# Audio.net
KiCad netlist of a schematic drawn in Altium Designer
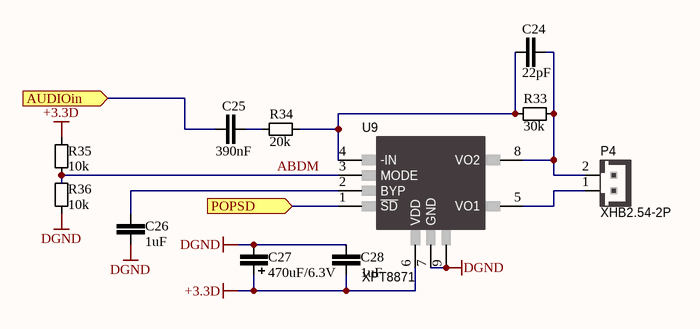
[diagram p0: Audio.SchDoc]

(export (version "E")
  (design (tool "Eeschema 10.0.6"))
  (components
    (comp (ref "C24")
      (value "22pF")
      (footprint "GreenBox:0603-C")
      (description "MLCC 22pF 5% 50V NPO 0603")
      (fields (field (name "Comment") "Cap") (field (name "PUBLISHER") "GreenBox"))
      (libsource (lib "Capacitor") (part "C11C022PJ1H0"))
    )
    (comp (ref "C25")
      (value "390nF")
      (footprint "GreenBox:0603-C")
      (description "MLCC 390nF 10% 50V X7R 0603")
      (fields (field (name "Comment") "Cap") (field (name "PUBLISHER") "GreenBox"))
      (libsource (lib "Capacitor") (part "C21C390NK1H0"))
    )
    (comp (ref "C26")
      (value "1uF")
      (footprint "GreenBox:0603-C")
      (description "MLCC 1uF 10% 16V X7R 0603")
      (fields (field (name "Comment") "Cap") (field (name "PUBLISHER") "GreenBox"))
      (libsource (lib "Capacitor") (part "C21C001UK1C0"))
    )
    (comp (ref "C27")
      (value "470uF/6.3V")
      (footprint "GreenBox:C-E-ALU-8X5")
      (description "DIP ECAP 470uF 20% 6.3V 8X5")
      (fields (field (name "Comment") "ECap") (field (name "PUBLISHER") "GreenBox"))
      (libsource (lib "Capacitor") (part "C3AD470UM0J0"))
    )
    (comp (ref "C28")
      (value "1uF")
      (footprint "GreenBox:0603-C")
      (description "MLCC 1uF 10% 16V X7R 0603")
      (fields (field (name "Comment") "Cap") (field (name "PUBLISHER") "GreenBox"))
      (libsource (lib "Capacitor") (part "C21C001UK1C0"))
    )
    (comp (ref "P4")
      (value "XHB2.54-2P")
      (footprint "GreenBox:XH-2")
      (description "Header XHB2.54-2P 2.54mm")
      (fields (field (name "PUBLISHER") "GreenBox"))
      (libsource (lib "Connectors") (part "P6DX02Z25400"))
    )
    (comp (ref "R33")
      (value "30k")
      (footprint "GreenBox:0603-R")
      (description "SMD Resistor 30k 1% 1/10W 0603 100PPM")
      (fields (field (name "Comment") "Res") (field (name "PUBLISHER") "GreenBox"))
      (libsource (lib "Resistor") (part "R11C030KFBF0"))
    )
    (comp (ref "R34")
      (value "20k")
      (footprint "GreenBox:0603-R")
      (description "SMD Resistor 20k 1% 1/10W 0603 100PPM")
      (fields (field (name "Comment") "Res") (field (name "PUBLISHER") "GreenBox"))
      (libsource (lib "Resistor") (part "R11C020KFBF0"))
    )
    (comp (ref "R35")
      (value "10k")
      (footprint "GreenBox:0603-R")
      (description "SMD Resistor 10k 1% 1/10W 0603 100PPM")
      (fields (field (name "Comment") "Res") (field (name "PUBLISHER") "GreenBox"))
      (libsource (lib "Resistor") (part "R11C010KFBF0"))
    )
    (comp (ref "R36")
      (value "10k")
      (footprint "GreenBox:0603-R")
      (description "SMD Resistor 10k 1% 1/10W 0603 100PPM")
      (fields (field (name "Comment") "Res") (field (name "PUBLISHER") "GreenBox"))
      (libsource (lib "Resistor") (part "R11C010KFBF0"))
    )
    (comp (ref "U9")
      (value "XPT8871")
      (footprint "GreenBox:SO-8_POWERPAD")
      (description "1 channel audio amplifier XPT8871 5W")
      (fields (field (name "MANUFACTURER") "XPTEK") (field (name "PUBLISHER") "GreenBox"))
      (libsource (lib "Semiconductor") (part "U1S1XPT88713"))
    )
  )
  (nets
    (net (code "1") (name "+3.3D") (class "Default")
      (node (ref "C27") (pin "1") (pinfunction "1_1") (pintype "passive"))
      (node (ref "C28") (pin "2") (pinfunction "2_2") (pintype "passive"))
      (node (ref "R35") (pin "1") (pinfunction "1_1") (pintype "passive"))
      (node (ref "U9") (pin "6") (pinfunction "VDD_6") (pintype "passive"))
    )
    (net (code "2") (name "/ABDM") (class "Default")
      (node (ref "R35") (pin "2") (pinfunction "2_2") (pintype "passive"))
      (node (ref "R36") (pin "1") (pinfunction "1_1") (pintype "passive"))
      (node (ref "U9") (pin "3") (pinfunction "MODE_3") (pintype "passive"))
    )
    (net (code "3") (name "/AUDIOin") (class "Default")
      (node (ref "C25") (pin "1") (pinfunction "1_1") (pintype "passive"))
    )
    (net (code "4") (name "/POPSD") (class "Default")
      (node (ref "U9") (pin "1") (pinfunction "~{SD}_1") (pintype "passive"))
    )
    (net (code "5") (name "DGND") (class "Default")
      (node (ref "C26") (pin "2") (pinfunction "2_2") (pintype "passive"))
      (node (ref "C27") (pin "2") (pinfunction "2_2") (pintype "passive"))
      (node (ref "C28") (pin "1") (pinfunction "1_1") (pintype "passive"))
      (node (ref "R36") (pin "2") (pinfunction "2_2") (pintype "passive"))
      (node (ref "U9") (pin "7") (pinfunction "GND_7") (pintype "passive"))
      (node (ref "U9") (pin "9") (pintype "passive"))
    )
    (net (code "6") (name "Net-(C25-Pad2)") (class "Default")
      (node (ref "C25") (pin "2") (pinfunction "2_2") (pintype "passive"))
      (node (ref "R34") (pin "1") (pinfunction "1_1") (pintype "passive"))
    )
    (net (code "7") (name "Net-(U9--IN)") (class "Default")
      (node (ref "C24") (pin "1") (pinfunction "1_1") (pintype "passive"))
      (node (ref "R33") (pin "1") (pinfunction "1_1") (pintype "passive"))
      (node (ref "R34") (pin "2") (pinfunction "2_2") (pintype "passive"))
      (node (ref "U9") (pin "4") (pinfunction "-IN_4") (pintype "passive"))
    )
    (net (code "8") (name "Net-(U9-BYP)") (class "Default")
      (node (ref "C26") (pin "1") (pinfunction "1_1") (pintype "passive"))
      (node (ref "U9") (pin "2") (pinfunction "BYP_2") (pintype "passive"))
    )
    (net (code "9") (name "Net-(U9-VO1)") (class "Default")
      (node (ref "P4") (pin "1") (pinfunction "1_1") (pintype "passive"))
      (node (ref "U9") (pin "5") (pinfunction "VO1_5") (pintype "passive"))
    )
    (net (code "10") (name "Net-(U9-VO2)") (class "Default")
      (node (ref "C24") (pin "2") (pinfunction "2_2") (pintype "passive"))
      (node (ref "P4") (pin "2") (pinfunction "2_2") (pintype "passive"))
      (node (ref "R33") (pin "2") (pinfunction "2_2") (pintype "passive"))
      (node (ref "U9") (pin "8") (pinfunction "VO2_8") (pintype "passive"))
    )
  )
)
